# all_proen2.net
KiCad netlist of a schematic drawn in EAGLE
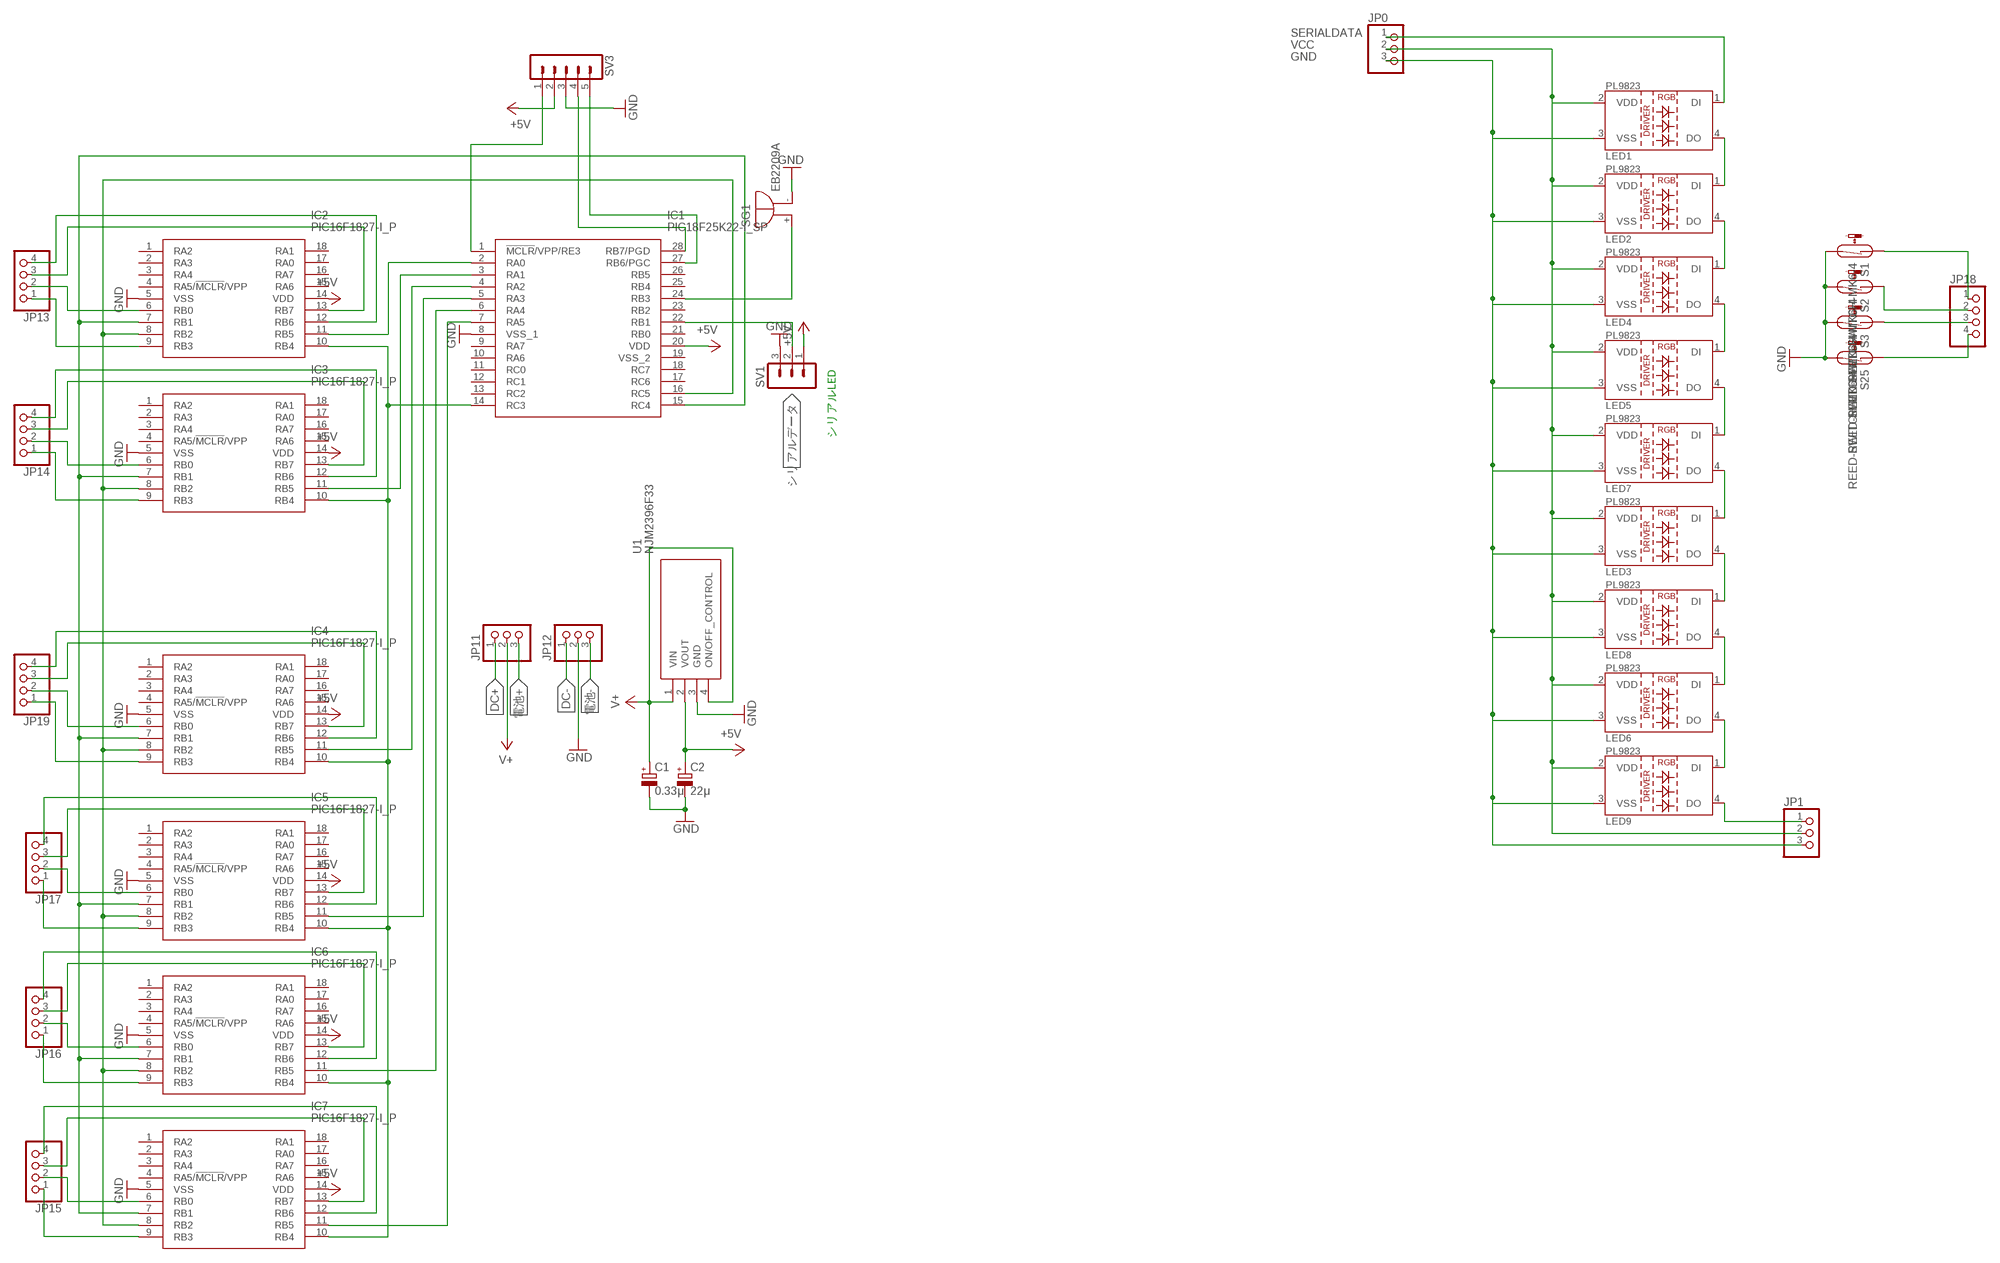
[diagram p0: schematic, sheet 1]

(export (version "E")
  (design (tool "Eeschema 10.0.6"))
  (components
    (comp (ref "C1")
      (value "0.33μ")
      (footprint "eagle-import:E2,5-6E")
      (libsource (lib "eagle-import") (part "CPOL-EUE2,5-6E"))
    )
    (comp (ref "C2")
      (value "22μ")
      (footprint "eagle-import:E2,5-6E")
      (libsource (lib "eagle-import") (part "CPOL-EUE2,5-6E"))
    )
    (comp (ref "IC1")
      (value "PIC18F25K22-I_SP")
      (footprint "eagle-import:DIP794W56P254L3486H508Q28N")
      (fields
        (field (name "MANUFACTURER_PART_NUMBER") "PIC18F25K22-I/SP")
        (field (name "MOUSER_PART_NUMBER") "579-PIC18F25K22ISP")
        (field (name "RS_PART_NUMBER") "8231142")
      )
      (libsource (lib "eagle-import") (part "PIC18F25K22-I_SP"))
    )
    (comp (ref "IC2")
      (value "PIC16F1827-I_P")
      (footprint "eagle-import:DIP794W56P254L2286H533Q18N")
      (fields
        (field (name "MANUFACTURER_PART_NUMBER") "PIC16F1827-I/P")
        (field (name "MOUSER_PART_NUMBER") "579-PIC16F1827-I/P")
        (field (name "RS_PART_NUMBER") "6988959P")
      )
      (libsource (lib "eagle-import") (part "PIC16F1827-I_P"))
    )
    (comp (ref "IC3")
      (value "PIC16F1827-I_P")
      (footprint "eagle-import:DIP794W56P254L2286H533Q18N")
      (fields
        (field (name "MANUFACTURER_PART_NUMBER") "PIC16F1827-I/P")
        (field (name "MOUSER_PART_NUMBER") "579-PIC16F1827-I/P")
        (field (name "RS_PART_NUMBER") "6988959P")
      )
      (libsource (lib "eagle-import") (part "PIC16F1827-I_P"))
    )
    (comp (ref "IC4")
      (value "PIC16F1827-I_P")
      (footprint "eagle-import:DIP794W56P254L2286H533Q18N")
      (fields
        (field (name "MANUFACTURER_PART_NUMBER") "PIC16F1827-I/P")
        (field (name "MOUSER_PART_NUMBER") "579-PIC16F1827-I/P")
        (field (name "RS_PART_NUMBER") "6988959P")
      )
      (libsource (lib "eagle-import") (part "PIC16F1827-I_P"))
    )
    (comp (ref "IC5")
      (value "PIC16F1827-I_P")
      (footprint "eagle-import:DIP794W56P254L2286H533Q18N")
      (fields
        (field (name "MANUFACTURER_PART_NUMBER") "PIC16F1827-I/P")
        (field (name "MOUSER_PART_NUMBER") "579-PIC16F1827-I/P")
        (field (name "RS_PART_NUMBER") "6988959P")
      )
      (libsource (lib "eagle-import") (part "PIC16F1827-I_P"))
    )
    (comp (ref "IC6")
      (value "PIC16F1827-I_P")
      (footprint "eagle-import:DIP794W56P254L2286H533Q18N")
      (fields
        (field (name "MANUFACTURER_PART_NUMBER") "PIC16F1827-I/P")
        (field (name "MOUSER_PART_NUMBER") "579-PIC16F1827-I/P")
        (field (name "RS_PART_NUMBER") "6988959P")
      )
      (libsource (lib "eagle-import") (part "PIC16F1827-I_P"))
    )
    (comp (ref "IC7")
      (value "PIC16F1827-I_P")
      (footprint "eagle-import:DIP794W56P254L2286H533Q18N")
      (fields
        (field (name "MANUFACTURER_PART_NUMBER") "PIC16F1827-I/P")
        (field (name "MOUSER_PART_NUMBER") "579-PIC16F1827-I/P")
        (field (name "RS_PART_NUMBER") "6988959P")
      )
      (libsource (lib "eagle-import") (part "PIC16F1827-I_P"))
    )
    (comp (ref "JP0")
      (value "PINHD-1X3")
      (footprint "eagle-import:1X03")
      (libsource (lib "eagle-import") (part "PINHD-1X3"))
    )
    (comp (ref "JP1")
      (value "PINHD-1X3")
      (footprint "eagle-import:1X03")
      (libsource (lib "eagle-import") (part "PINHD-1X3"))
    )
    (comp (ref "JP11")
      (value "PINHD-1X3")
      (footprint "eagle-import:1X03")
      (libsource (lib "eagle-import") (part "PINHD-1X3"))
    )
    (comp (ref "JP12")
      (value "PINHD-1X3")
      (footprint "eagle-import:1X03")
      (libsource (lib "eagle-import") (part "PINHD-1X3"))
    )
    (comp (ref "JP13")
      (value "PINHD-1X4")
      (footprint "eagle-import:1X04")
      (libsource (lib "eagle-import") (part "PINHD-1X4"))
    )
    (comp (ref "JP14")
      (value "PINHD-1X4")
      (footprint "eagle-import:1X04")
      (libsource (lib "eagle-import") (part "PINHD-1X4"))
    )
    (comp (ref "JP15")
      (value "PINHD-1X4")
      (footprint "eagle-import:1X04")
      (libsource (lib "eagle-import") (part "PINHD-1X4"))
    )
    (comp (ref "JP16")
      (value "PINHD-1X4")
      (footprint "eagle-import:1X04")
      (libsource (lib "eagle-import") (part "PINHD-1X4"))
    )
    (comp (ref "JP17")
      (value "PINHD-1X4")
      (footprint "eagle-import:1X04")
      (libsource (lib "eagle-import") (part "PINHD-1X4"))
    )
    (comp (ref "JP18")
      (value "PINHD-1X4")
      (footprint "eagle-import:1X04")
      (libsource (lib "eagle-import") (part "PINHD-1X4"))
    )
    (comp (ref "JP19")
      (value "PINHD-1X4")
      (footprint "eagle-import:1X04")
      (libsource (lib "eagle-import") (part "PINHD-1X4"))
    )
    (comp (ref "LED1")
      (value "LED-PL9823-F5")
      (footprint "eagle-import:LED-PL9823-F5")
      (libsource (lib "eagle-import") (part "LED-PL9823-F5"))
    )
    (comp (ref "LED2")
      (value "LED-PL9823-F5")
      (footprint "eagle-import:LED-PL9823-F5")
      (libsource (lib "eagle-import") (part "LED-PL9823-F5"))
    )
    (comp (ref "LED3")
      (value "LED-PL9823-F5")
      (footprint "eagle-import:LED-PL9823-F5")
      (libsource (lib "eagle-import") (part "LED-PL9823-F5"))
    )
    (comp (ref "LED4")
      (value "LED-PL9823-F5")
      (footprint "eagle-import:LED-PL9823-F5")
      (libsource (lib "eagle-import") (part "LED-PL9823-F5"))
    )
    (comp (ref "LED5")
      (value "LED-PL9823-F5")
      (footprint "eagle-import:LED-PL9823-F5")
      (libsource (lib "eagle-import") (part "LED-PL9823-F5"))
    )
    (comp (ref "LED6")
      (value "LED-PL9823-F5")
      (footprint "eagle-import:LED-PL9823-F5")
      (libsource (lib "eagle-import") (part "LED-PL9823-F5"))
    )
    (comp (ref "LED7")
      (value "LED-PL9823-F5")
      (footprint "eagle-import:LED-PL9823-F5")
      (libsource (lib "eagle-import") (part "LED-PL9823-F5"))
    )
    (comp (ref "LED8")
      (value "LED-PL9823-F5")
      (footprint "eagle-import:LED-PL9823-F5")
      (libsource (lib "eagle-import") (part "LED-PL9823-F5"))
    )
    (comp (ref "LED9")
      (value "LED-PL9823-F5")
      (footprint "eagle-import:LED-PL9823-F5")
      (libsource (lib "eagle-import") (part "LED-PL9823-F5"))
    )
    (comp (ref "S1")
      (value "REED-SWITCH-MK6-4")
      (footprint "eagle-import:MK6-4")
      (libsource (lib "eagle-import") (part "REED-SWITCH-MK6-4"))
    )
    (comp (ref "S2")
      (value "REED-SWITCH-MK6-4")
      (footprint "eagle-import:MK6-4")
      (libsource (lib "eagle-import") (part "REED-SWITCH-MK6-4"))
    )
    (comp (ref "S3")
      (value "REED-SWITCH-MK6-4")
      (footprint "eagle-import:MK6-4")
      (libsource (lib "eagle-import") (part "REED-SWITCH-MK6-4"))
    )
    (comp (ref "S25")
      (value "REED-SWITCH-MK6-4")
      (footprint "eagle-import:MK6-4")
      (libsource (lib "eagle-import") (part "REED-SWITCH-MK6-4"))
    )
    (comp (ref "SG1")
      (value "EB2209A")
      (footprint "eagle-import:EB2209A")
      (libsource (lib "eagle-import") (part "EB2209A"))
    )
    (comp (ref "SV1")
      (value "MA03-1")
      (footprint "eagle-import:MA03-1")
      (libsource (lib "eagle-import") (part "MA03-1"))
    )
    (comp (ref "SV3")
      (value "MA05-1")
      (footprint "eagle-import:MA05-1")
      (libsource (lib "eagle-import") (part "MA05-1"))
    )
    (comp (ref "U1")
      (value "NJM2396F33")
      (footprint "eagle-import:TO254P480X1000X1900-4P")
      (fields (field (name "RS_PART_NUMBER") "6641023"))
      (libsource (lib "eagle-import") (part "NJM2396F33"))
    )
  )
  (nets
    (net (code "1") (name "+5V") (class "Default")
      (node (ref "C2") (pin "+") (pinfunction "+_+") (pintype "passive"))
      (node (ref "IC1") (pin "20") (pinfunction "VDD_20") (pintype "bidirectional"))
      (node (ref "IC2") (pin "14") (pinfunction "VDD_14") (pintype "bidirectional"))
      (node (ref "IC3") (pin "14") (pinfunction "VDD_14") (pintype "bidirectional"))
      (node (ref "IC4") (pin "14") (pinfunction "VDD_14") (pintype "bidirectional"))
      (node (ref "IC5") (pin "14") (pinfunction "VDD_14") (pintype "bidirectional"))
      (node (ref "IC6") (pin "14") (pinfunction "VDD_14") (pintype "bidirectional"))
      (node (ref "IC7") (pin "14") (pinfunction "VDD_14") (pintype "bidirectional"))
      (node (ref "SV1") (pin "1") (pinfunction "1_1") (pintype "passive"))
      (node (ref "SV3") (pin "2") (pinfunction "2_2") (pintype "passive"))
      (node (ref "U1") (pin "2") (pinfunction "VOUT_2") (pintype "bidirectional"))
    )
    (net (code "2") (name "/SERIALDATA") (class "Default")
      (node (ref "JP0") (pin "1") (pinfunction "1_1") (pintype "passive"))
      (node (ref "LED1") (pin "1") (pinfunction "DI_1") (pintype "bidirectional"))
    )
    (net (code "3") (name "/VCC") (class "Default")
      (node (ref "JP0") (pin "2") (pinfunction "2_2") (pintype "passive"))
      (node (ref "JP1") (pin "2") (pinfunction "2_2") (pintype "passive"))
      (node (ref "LED1") (pin "2") (pinfunction "VDD_2") (pintype "bidirectional"))
      (node (ref "LED2") (pin "2") (pinfunction "VDD_2") (pintype "bidirectional"))
      (node (ref "LED3") (pin "2") (pinfunction "VDD_2") (pintype "bidirectional"))
      (node (ref "LED4") (pin "2") (pinfunction "VDD_2") (pintype "bidirectional"))
      (node (ref "LED5") (pin "2") (pinfunction "VDD_2") (pintype "bidirectional"))
      (node (ref "LED6") (pin "2") (pinfunction "VDD_2") (pintype "bidirectional"))
      (node (ref "LED7") (pin "2") (pinfunction "VDD_2") (pintype "bidirectional"))
      (node (ref "LED8") (pin "2") (pinfunction "VDD_2") (pintype "bidirectional"))
      (node (ref "LED9") (pin "2") (pinfunction "VDD_2") (pintype "bidirectional"))
    )
    (net (code "4") (name "DC+") (class "Default")
      (node (ref "JP11") (pin "1") (pinfunction "1_1") (pintype "passive"))
    )
    (net (code "5") (name "DC-") (class "Default")
      (node (ref "JP12") (pin "1") (pinfunction "1_1") (pintype "passive"))
    )
    (net (code "6") (name "GND") (class "Default")
      (node (ref "C1") (pin "-") (pinfunction "-_-") (pintype "passive"))
      (node (ref "C2") (pin "-") (pinfunction "-_-") (pintype "passive"))
      (node (ref "IC1") (pin "8") (pinfunction "VSS_1_8") (pintype "bidirectional"))
      (node (ref "IC2") (pin "5") (pinfunction "VSS_5") (pintype "bidirectional"))
      (node (ref "IC3") (pin "5") (pinfunction "VSS_5") (pintype "bidirectional"))
      (node (ref "IC4") (pin "5") (pinfunction "VSS_5") (pintype "bidirectional"))
      (node (ref "IC5") (pin "5") (pinfunction "VSS_5") (pintype "bidirectional"))
      (node (ref "IC6") (pin "5") (pinfunction "VSS_5") (pintype "bidirectional"))
      (node (ref "IC7") (pin "5") (pinfunction "VSS_5") (pintype "bidirectional"))
      (node (ref "JP0") (pin "3") (pinfunction "3_3") (pintype "passive"))
      (node (ref "JP1") (pin "3") (pinfunction "3_3") (pintype "passive"))
      (node (ref "JP12") (pin "2") (pinfunction "2_2") (pintype "passive"))
      (node (ref "LED1") (pin "3") (pinfunction "VSS_3") (pintype "bidirectional"))
      (node (ref "LED2") (pin "3") (pinfunction "VSS_3") (pintype "bidirectional"))
      (node (ref "LED3") (pin "3") (pinfunction "VSS_3") (pintype "bidirectional"))
      (node (ref "LED4") (pin "3") (pinfunction "VSS_3") (pintype "bidirectional"))
      (node (ref "LED5") (pin "3") (pinfunction "VSS_3") (pintype "bidirectional"))
      (node (ref "LED6") (pin "3") (pinfunction "VSS_3") (pintype "bidirectional"))
      (node (ref "LED7") (pin "3") (pinfunction "VSS_3") (pintype "bidirectional"))
      (node (ref "LED8") (pin "3") (pinfunction "VSS_3") (pintype "bidirectional"))
      (node (ref "LED9") (pin "3") (pinfunction "VSS_3") (pintype "bidirectional"))
      (node (ref "S1") (pin "2") (pinfunction "2_2") (pintype "passive"))
      (node (ref "S2") (pin "2") (pinfunction "2_2") (pintype "passive"))
      (node (ref "S25") (pin "2") (pinfunction "2_2") (pintype "passive"))
      (node (ref "S3") (pin "2") (pinfunction "2_2") (pintype "passive"))
      (node (ref "SG1") (pin "-") (pinfunction "-_-") (pintype "passive"))
      (node (ref "SV1") (pin "3") (pinfunction "3_3") (pintype "passive"))
      (node (ref "SV3") (pin "3") (pinfunction "3_3") (pintype "passive"))
      (node (ref "U1") (pin "3") (pinfunction "GND_3") (pintype "bidirectional"))
    )
    (net (code "7") (name "Net-(IC1-RA0)") (class "Default")
      (node (ref "IC1") (pin "2") (pinfunction "RA0_2") (pintype "bidirectional"))
      (node (ref "IC2") (pin "11") (pinfunction "RB5_11") (pintype "bidirectional"))
    )
    (net (code "8") (name "Net-(IC1-RA1)") (class "Default")
      (node (ref "IC1") (pin "3") (pinfunction "RA1_3") (pintype "bidirectional"))
      (node (ref "IC3") (pin "11") (pinfunction "RB5_11") (pintype "bidirectional"))
    )
    (net (code "9") (name "Net-(IC1-RA2)") (class "Default")
      (node (ref "IC1") (pin "4") (pinfunction "RA2_4") (pintype "bidirectional"))
      (node (ref "IC4") (pin "11") (pinfunction "RB5_11") (pintype "bidirectional"))
    )
    (net (code "10") (name "Net-(IC1-RA3)") (class "Default")
      (node (ref "IC1") (pin "5") (pinfunction "RA3_5") (pintype "bidirectional"))
      (node (ref "IC5") (pin "11") (pinfunction "RB5_11") (pintype "bidirectional"))
    )
    (net (code "11") (name "Net-(IC1-RA4)") (class "Default")
      (node (ref "IC1") (pin "6") (pinfunction "RA4_6") (pintype "bidirectional"))
      (node (ref "IC6") (pin "11") (pinfunction "RB5_11") (pintype "bidirectional"))
    )
    (net (code "12") (name "Net-(IC1-RA5)") (class "Default")
      (node (ref "IC1") (pin "7") (pinfunction "RA5_7") (pintype "bidirectional"))
      (node (ref "IC7") (pin "11") (pinfunction "RB5_11") (pintype "bidirectional"))
    )
    (net (code "13") (name "Net-(IC1-RB3)") (class "Default")
      (node (ref "IC1") (pin "24") (pinfunction "RB3_24") (pintype "bidirectional"))
      (node (ref "SG1") (pin "+") (pinfunction "+_+") (pintype "passive"))
    )
    (net (code "14") (name "Net-(IC1-RB6{slash}PGC)") (class "Default")
      (node (ref "IC1") (pin "27") (pinfunction "RB6/PGC_27") (pintype "bidirectional"))
      (node (ref "SV3") (pin "5") (pinfunction "5_5") (pintype "passive"))
    )
    (net (code "15") (name "Net-(IC1-RB7{slash}PGD)") (class "Default")
      (node (ref "IC1") (pin "28") (pinfunction "RB7/PGD_28") (pintype "bidirectional"))
      (node (ref "SV3") (pin "4") (pinfunction "4_4") (pintype "passive"))
    )
    (net (code "16") (name "Net-(IC1-RC3)") (class "Default")
      (node (ref "IC1") (pin "14") (pinfunction "RC3_14") (pintype "bidirectional"))
      (node (ref "IC2") (pin "10") (pinfunction "RB4_10") (pintype "bidirectional"))
      (node (ref "IC3") (pin "10") (pinfunction "RB4_10") (pintype "bidirectional"))
      (node (ref "IC4") (pin "10") (pinfunction "RB4_10") (pintype "bidirectional"))
      (node (ref "IC5") (pin "10") (pinfunction "RB4_10") (pintype "bidirectional"))
      (node (ref "IC6") (pin "10") (pinfunction "RB4_10") (pintype "bidirectional"))
      (node (ref "IC7") (pin "10") (pinfunction "RB4_10") (pintype "bidirectional"))
    )
    (net (code "17") (name "Net-(IC1-RC4)") (class "Default")
      (node (ref "IC1") (pin "15") (pinfunction "RC4_15") (pintype "bidirectional"))
      (node (ref "IC2") (pin "7") (pinfunction "RB1_7") (pintype "bidirectional"))
      (node (ref "IC3") (pin "7") (pinfunction "RB1_7") (pintype "bidirectional"))
      (node (ref "IC4") (pin "7") (pinfunction "RB1_7") (pintype "bidirectional"))
      (node (ref "IC5") (pin "7") (pinfunction "RB1_7") (pintype "bidirectional"))
      (node (ref "IC6") (pin "7") (pinfunction "RB1_7") (pintype "bidirectional"))
      (node (ref "IC7") (pin "7") (pinfunction "RB1_7") (pintype "bidirectional"))
    )
    (net (code "18") (name "Net-(IC1-RC5)") (class "Default")
      (node (ref "IC1") (pin "16") (pinfunction "RC5_16") (pintype "bidirectional"))
      (node (ref "IC2") (pin "8") (pinfunction "RB2_8") (pintype "bidirectional"))
      (node (ref "IC3") (pin "8") (pinfunction "RB2_8") (pintype "bidirectional"))
      (node (ref "IC4") (pin "8") (pinfunction "RB2_8") (pintype "bidirectional"))
      (node (ref "IC5") (pin "8") (pinfunction "RB2_8") (pintype "bidirectional"))
      (node (ref "IC6") (pin "8") (pinfunction "RB2_8") (pintype "bidirectional"))
      (node (ref "IC7") (pin "8") (pinfunction "RB2_8") (pintype "bidirectional"))
    )
    (net (code "19") (name "Net-(IC1-~{MCLR}{slash}VPP{slash}RE3)") (class "Default")
      (node (ref "IC1") (pin "1") (pinfunction "~{MCLR}/VPP/RE3_1") (pintype "bidirectional"))
      (node (ref "SV3") (pin "1") (pinfunction "1_1") (pintype "passive"))
    )
    (net (code "20") (name "Net-(IC2-RB0)") (class "Default")
      (node (ref "IC2") (pin "6") (pinfunction "RB0_6") (pintype "bidirectional"))
      (node (ref "JP13") (pin "2") (pinfunction "2_2") (pintype "passive"))
    )
    (net (code "21") (name "Net-(IC2-RB3)") (class "Default")
      (node (ref "IC2") (pin "9") (pinfunction "RB3_9") (pintype "bidirectional"))
      (node (ref "JP13") (pin "1") (pinfunction "1_1") (pintype "passive"))
    )
    (net (code "22") (name "Net-(IC2-RB6)") (class "Default")
      (node (ref "IC2") (pin "12") (pinfunction "RB6_12") (pintype "bidirectional"))
      (node (ref "JP13") (pin "4") (pinfunction "4_4") (pintype "passive"))
    )
    (net (code "23") (name "Net-(IC2-RB7)") (class "Default")
      (node (ref "IC2") (pin "13") (pinfunction "RB7_13") (pintype "bidirectional"))
      (node (ref "JP13") (pin "3") (pinfunction "3_3") (pintype "passive"))
    )
    (net (code "24") (name "Net-(IC3-RB0)") (class "Default")
      (node (ref "IC3") (pin "6") (pinfunction "RB0_6") (pintype "bidirectional"))
      (node (ref "JP14") (pin "2") (pinfunction "2_2") (pintype "passive"))
    )
    (net (code "25") (name "Net-(IC3-RB3)") (class "Default")
      (node (ref "IC3") (pin "9") (pinfunction "RB3_9") (pintype "bidirectional"))
      (node (ref "JP14") (pin "1") (pinfunction "1_1") (pintype "passive"))
    )
    (net (code "26") (name "Net-(IC3-RB6)") (class "Default")
      (node (ref "IC3") (pin "12") (pinfunction "RB6_12") (pintype "bidirectional"))
      (node (ref "JP14") (pin "4") (pinfunction "4_4") (pintype "passive"))
    )
    (net (code "27") (name "Net-(IC3-RB7)") (class "Default")
      (node (ref "IC3") (pin "13") (pinfunction "RB7_13") (pintype "bidirectional"))
      (node (ref "JP14") (pin "3") (pinfunction "3_3") (pintype "passive"))
    )
    (net (code "28") (name "Net-(IC4-RB0)") (class "Default")
      (node (ref "IC4") (pin "6") (pinfunction "RB0_6") (pintype "bidirectional"))
      (node (ref "JP19") (pin "2") (pinfunction "2_2") (pintype "passive"))
    )
    (net (code "29") (name "Net-(IC4-RB3)") (class "Default")
      (node (ref "IC4") (pin "9") (pinfunction "RB3_9") (pintype "bidirectional"))
      (node (ref "JP19") (pin "1") (pinfunction "1_1") (pintype "passive"))
    )
    (net (code "30") (name "Net-(IC4-RB6)") (class "Default")
      (node (ref "IC4") (pin "12") (pinfunction "RB6_12") (pintype "bidirectional"))
      (node (ref "JP19") (pin "4") (pinfunction "4_4") (pintype "passive"))
    )
    (net (code "31") (name "Net-(IC4-RB7)") (class "Default")
      (node (ref "IC4") (pin "13") (pinfunction "RB7_13") (pintype "bidirectional"))
      (node (ref "JP19") (pin "3") (pinfunction "3_3") (pintype "passive"))
    )
    (net (code "32") (name "Net-(IC5-RB0)") (class "Default")
      (node (ref "IC5") (pin "6") (pinfunction "RB0_6") (pintype "bidirectional"))
      (node (ref "JP17") (pin "2") (pinfunction "2_2") (pintype "passive"))
    )
    (net (code "33") (name "Net-(IC5-RB3)") (class "Default")
      (node (ref "IC5") (pin "9") (pinfunction "RB3_9") (pintype "bidirectional"))
      (node (ref "JP17") (pin "1") (pinfunction "1_1") (pintype "passive"))
    )
    (net (code "34") (name "Net-(IC5-RB6)") (class "Default")
      (node (ref "IC5") (pin "12") (pinfunction "RB6_12") (pintype "bidirectional"))
      (node (ref "JP17") (pin "4") (pinfunction "4_4") (pintype "passive"))
    )
    (net (code "35") (name "Net-(IC5-RB7)") (class "Default")
      (node (ref "IC5") (pin "13") (pinfunction "RB7_13") (pintype "bidirectional"))
      (node (ref "JP17") (pin "3") (pinfunction "3_3") (pintype "passive"))
    )
    (net (code "36") (name "Net-(IC6-RB0)") (class "Default")
      (node (ref "IC6") (pin "6") (pinfunction "RB0_6") (pintype "bidirectional"))
      (node (ref "JP16") (pin "2") (pinfunction "2_2") (pintype "passive"))
    )
    (net (code "37") (name "Net-(IC6-RB3)") (class "Default")
      (node (ref "IC6") (pin "9") (pinfunction "RB3_9") (pintype "bidirectional"))
      (node (ref "JP16") (pin "1") (pinfunction "1_1") (pintype "passive"))
    )
    (net (code "38") (name "Net-(IC6-RB6)") (class "Default")
      (node (ref "IC6") (pin "12") (pinfunction "RB6_12") (pintype "bidirectional"))
      (node (ref "JP16") (pin "4") (pinfunction "4_4") (pintype "passive"))
    )
    (net (code "39") (name "Net-(IC6-RB7)") (class "Default")
      (node (ref "IC6") (pin "13") (pinfunction "RB7_13") (pintype "bidirectional"))
      (node (ref "JP16") (pin "3") (pinfunction "3_3") (pintype "passive"))
    )
    (net (code "40") (name "Net-(IC7-RB0)") (class "Default")
      (node (ref "IC7") (pin "6") (pinfunction "RB0_6") (pintype "bidirectional"))
      (node (ref "JP15") (pin "2") (pinfunction "2_2") (pintype "passive"))
    )
    (net (code "41") (name "Net-(IC7-RB3)") (class "Default")
      (node (ref "IC7") (pin "9") (pinfunction "RB3_9") (pintype "bidirectional"))
      (node (ref "JP15") (pin "1") (pinfunction "1_1") (pintype "passive"))
    )
    (net (code "42") (name "Net-(IC7-RB6)") (class "Default")
      (node (ref "IC7") (pin "12") (pinfunction "RB6_12") (pintype "bidirectional"))
      (node (ref "JP15") (pin "4") (pinfunction "4_4") (pintype "passive"))
    )
    (net (code "43") (name "Net-(IC7-RB7)") (class "Default")
      (node (ref "IC7") (pin "13") (pinfunction "RB7_13") (pintype "bidirectional"))
      (node (ref "JP15") (pin "3") (pinfunction "3_3") (pintype "passive"))
    )
    (net (code "44") (name "Net-(JP18-Pad1)") (class "Default")
      (node (ref "JP18") (pin "1") (pinfunction "1_1") (pintype "passive"))
      (node (ref "S1") (pin "1") (pinfunction "1_1") (pintype "passive"))
    )
    (net (code "45") (name "Net-(JP18-Pad2)") (class "Default")
      (node (ref "JP18") (pin "2") (pinfunction "2_2") (pintype "passive"))
      (node (ref "S2") (pin "1") (pinfunction "1_1") (pintype "passive"))
    )
    (net (code "46") (name "Net-(JP18-Pad3)") (class "Default")
      (node (ref "JP18") (pin "3") (pinfunction "3_3") (pintype "passive"))
      (node (ref "S3") (pin "1") (pinfunction "1_1") (pintype "passive"))
    )
    (net (code "47") (name "Net-(JP18-Pad4)") (class "Default")
      (node (ref "JP18") (pin "4") (pinfunction "4_4") (pintype "passive"))
      (node (ref "S25") (pin "1") (pinfunction "1_1") (pintype "passive"))
    )
    (net (code "48") (name "Net-(LED1-DO)") (class "Default")
      (node (ref "LED1") (pin "4") (pinfunction "DO_4") (pintype "bidirectional"))
      (node (ref "LED2") (pin "1") (pinfunction "DI_1") (pintype "bidirectional"))
    )
    (net (code "49") (name "Net-(LED2-DO)") (class "Default")
      (node (ref "LED2") (pin "4") (pinfunction "DO_4") (pintype "bidirectional"))
      (node (ref "LED4") (pin "1") (pinfunction "DI_1") (pintype "bidirectional"))
    )
    (net (code "50") (name "Net-(LED3-DI)") (class "Default")
      (node (ref "LED3") (pin "1") (pinfunction "DI_1") (pintype "bidirectional"))
      (node (ref "LED7") (pin "4") (pinfunction "DO_4") (pintype "bidirectional"))
    )
    (net (code "51") (name "Net-(LED3-DO)") (class "Default")
      (node (ref "LED3") (pin "4") (pinfunction "DO_4") (pintype "bidirectional"))
      (node (ref "LED8") (pin "1") (pinfunction "DI_1") (pintype "bidirectional"))
    )
    (net (code "52") (name "Net-(LED4-DO)") (class "Default")
      (node (ref "LED4") (pin "4") (pinfunction "DO_4") (pintype "bidirectional"))
      (node (ref "LED5") (pin "1") (pinfunction "DI_1") (pintype "bidirectional"))
    )
    (net (code "53") (name "Net-(LED5-DO)") (class "Default")
      (node (ref "LED5") (pin "4") (pinfunction "DO_4") (pintype "bidirectional"))
      (node (ref "LED7") (pin "1") (pinfunction "DI_1") (pintype "bidirectional"))
    )
    (net (code "54") (name "Net-(LED6-DI)") (class "Default")
      (node (ref "LED6") (pin "1") (pinfunction "DI_1") (pintype "bidirectional"))
      (node (ref "LED8") (pin "4") (pinfunction "DO_4") (pintype "bidirectional"))
    )
    (net (code "55") (name "Net-(LED6-DO)") (class "Default")
      (node (ref "LED6") (pin "4") (pinfunction "DO_4") (pintype "bidirectional"))
      (node (ref "LED9") (pin "1") (pinfunction "DI_1") (pintype "bidirectional"))
    )
    (net (code "56") (name "Net-(LED9-DO)") (class "Default")
      (node (ref "JP1") (pin "1") (pinfunction "1_1") (pintype "passive"))
      (node (ref "LED9") (pin "4") (pinfunction "DO_4") (pintype "bidirectional"))
    )
    (net (code "57") (name "V+") (class "Default")
      (node (ref "C1") (pin "+") (pinfunction "+_+") (pintype "passive"))
      (node (ref "JP11") (pin "2") (pinfunction "2_2") (pintype "passive"))
      (node (ref "U1") (pin "1") (pinfunction "VIN_1") (pintype "bidirectional"))
      (node (ref "U1") (pin "4") (pinfunction "ON/OFF_CONTROL_4") (pintype "bidirectional"))
    )
    (net (code "58") (name "unconnected-(IC1-RA6-Pad10)") (class "Default")
      (node (ref "IC1") (pin "10") (pinfunction "RA6_10") (pintype "bidirectional"))
    )
    (net (code "59") (name "unconnected-(IC1-RA7-Pad9)") (class "Default")
      (node (ref "IC1") (pin "9") (pinfunction "RA7_9") (pintype "bidirectional"))
    )
    (net (code "60") (name "unconnected-(IC1-RB0-Pad21)") (class "Default")
      (node (ref "IC1") (pin "21") (pinfunction "RB0_21") (pintype "bidirectional"))
    )
    (net (code "61") (name "unconnected-(IC1-RB2-Pad23)") (class "Default")
      (node (ref "IC1") (pin "23") (pinfunction "RB2_23") (pintype "bidirectional"))
    )
    (net (code "62") (name "unconnected-(IC1-RB4-Pad25)") (class "Default")
      (node (ref "IC1") (pin "25") (pinfunction "RB4_25") (pintype "bidirectional"))
    )
    (net (code "63") (name "unconnected-(IC1-RB5-Pad26)") (class "Default")
      (node (ref "IC1") (pin "26") (pinfunction "RB5_26") (pintype "bidirectional"))
    )
    (net (code "64") (name "unconnected-(IC1-RC0-Pad11)") (class "Default")
      (node (ref "IC1") (pin "11") (pinfunction "RC0_11") (pintype "bidirectional"))
    )
    (net (code "65") (name "unconnected-(IC1-RC1-Pad12)") (class "Default")
      (node (ref "IC1") (pin "12") (pinfunction "RC1_12") (pintype "bidirectional"))
    )
    (net (code "66") (name "unconnected-(IC1-RC2-Pad13)") (class "Default")
      (node (ref "IC1") (pin "13") (pinfunction "RC2_13") (pintype "bidirectional"))
    )
    (net (code "67") (name "unconnected-(IC1-RC6-Pad17)") (class "Default")
      (node (ref "IC1") (pin "17") (pinfunction "RC6_17") (pintype "bidirectional"))
    )
    (net (code "68") (name "unconnected-(IC1-RC7-Pad18)") (class "Default")
      (node (ref "IC1") (pin "18") (pinfunction "RC7_18") (pintype "bidirectional"))
    )
    (net (code "69") (name "unconnected-(IC1-VSS_2-Pad19)") (class "Default")
      (node (ref "IC1") (pin "19") (pinfunction "VSS_2_19") (pintype "bidirectional"))
    )
    (net (code "70") (name "unconnected-(IC2-RA0-Pad17)") (class "Default")
      (node (ref "IC2") (pin "17") (pinfunction "RA0_17") (pintype "bidirectional"))
    )
    (net (code "71") (name "unconnected-(IC2-RA1-Pad18)") (class "Default")
      (node (ref "IC2") (pin "18") (pinfunction "RA1_18") (pintype "bidirectional"))
    )
    (net (code "72") (name "unconnected-(IC2-RA2-Pad1)") (class "Default")
      (node (ref "IC2") (pin "1") (pinfunction "RA2_1") (pintype "bidirectional"))
    )
    (net (code "73") (name "unconnected-(IC2-RA3-Pad2)") (class "Default")
      (node (ref "IC2") (pin "2") (pinfunction "RA3_2") (pintype "bidirectional"))
    )
    (net (code "74") (name "unconnected-(IC2-RA4-Pad3)") (class "Default")
      (node (ref "IC2") (pin "3") (pinfunction "RA4_3") (pintype "bidirectional"))
    )
    (net (code "75") (name "unconnected-(IC2-RA5{slash}~{MCLR}{slash}VPP-Pad4)") (class "Default")
      (node (ref "IC2") (pin "4") (pinfunction "RA5/~{MCLR}/VPP_4") (pintype "bidirectional"))
    )
    (net (code "76") (name "unconnected-(IC2-RA6-Pad15)") (class "Default")
      (node (ref "IC2") (pin "15") (pinfunction "RA6_15") (pintype "bidirectional"))
    )
    (net (code "77") (name "unconnected-(IC2-RA7-Pad16)") (class "Default")
      (node (ref "IC2") (pin "16") (pinfunction "RA7_16") (pintype "bidirectional"))
    )
    (net (code "78") (name "unconnected-(IC3-RA0-Pad17)") (class "Default")
      (node (ref "IC3") (pin "17") (pinfunction "RA0_17") (pintype "bidirectional"))
    )
    (net (code "79") (name "unconnected-(IC3-RA1-Pad18)") (class "Default")
      (node (ref "IC3") (pin "18") (pinfunction "RA1_18") (pintype "bidirectional"))
    )
    (net (code "80") (name "unconnected-(IC3-RA2-Pad1)") (class "Default")
      (node (ref "IC3") (pin "1") (pinfunction "RA2_1") (pintype "bidirectional"))
    )
    (net (code "81") (name "unconnected-(IC3-RA3-Pad2)") (class "Default")
      (node (ref "IC3") (pin "2") (pinfunction "RA3_2") (pintype "bidirectional"))
    )
    (net (code "82") (name "unconnected-(IC3-RA4-Pad3)") (class "Default")
      (node (ref "IC3") (pin "3") (pinfunction "RA4_3") (pintype "bidirectional"))
    )
    (net (code "83") (name "unconnected-(IC3-RA5{slash}~{MCLR}{slash}VPP-Pad4)") (class "Default")
      (node (ref "IC3") (pin "4") (pinfunction "RA5/~{MCLR}/VPP_4") (pintype "bidirectional"))
    )
    (net (code "84") (name "unconnected-(IC3-RA6-Pad15)") (class "Default")
      (node (ref "IC3") (pin "15") (pinfunction "RA6_15") (pintype "bidirectional"))
    )
    (net (code "85") (name "unconnected-(IC3-RA7-Pad16)") (class "Default")
      (node (ref "IC3") (pin "16") (pinfunction "RA7_16") (pintype "bidirectional"))
    )
    (net (code "86") (name "unconnected-(IC4-RA0-Pad17)") (class "Default")
      (node (ref "IC4") (pin "17") (pinfunction "RA0_17") (pintype "bidirectional"))
    )
    (net (code "87") (name "unconnected-(IC4-RA1-Pad18)") (class "Default")
      (node (ref "IC4") (pin "18") (pinfunction "RA1_18") (pintype "bidirectional"))
    )
    (net (code "88") (name "unconnected-(IC4-RA2-Pad1)") (class "Default")
      (node (ref "IC4") (pin "1") (pinfunction "RA2_1") (pintype "bidirectional"))
    )
    (net (code "89") (name "unconnected-(IC4-RA3-Pad2)") (class "Default")
      (node (ref "IC4") (pin "2") (pinfunction "RA3_2") (pintype "bidirectional"))
    )
    (net (code "90") (name "unconnected-(IC4-RA4-Pad3)") (class "Default")
      (node (ref "IC4") (pin "3") (pinfunction "RA4_3") (pintype "bidirectional"))
    )
    (net (code "91") (name "unconnected-(IC4-RA5{slash}~{MCLR}{slash}VPP-Pad4)") (class "Default")
      (node (ref "IC4") (pin "4") (pinfunction "RA5/~{MCLR}/VPP_4") (pintype "bidirectional"))
    )
    (net (code "92") (name "unconnected-(IC4-RA6-Pad15)") (class "Default")
      (node (ref "IC4") (pin "15") (pinfunction "RA6_15") (pintype "bidirectional"))
    )
    (net (code "93") (name "unconnected-(IC4-RA7-Pad16)") (class "Default")
      (node (ref "IC4") (pin "16") (pinfunction "RA7_16") (pintype "bidirectional"))
    )
    (net (code "94") (name "unconnected-(IC5-RA0-Pad17)") (class "Default")
      (node (ref "IC5") (pin "17") (pinfunction "RA0_17") (pintype "bidirectional"))
    )
    (net (code "95") (name "unconnected-(IC5-RA1-Pad18)") (class "Default")
      (node (ref "IC5") (pin "18") (pinfunction "RA1_18") (pintype "bidirectional"))
    )
    (net (code "96") (name "unconnected-(IC5-RA2-Pad1)") (class "Default")
      (node (ref "IC5") (pin "1") (pinfunction "RA2_1") (pintype "bidirectional"))
    )
    (net (code "97") (name "unconnected-(IC5-RA3-Pad2)") (class "Default")
      (node (ref "IC5") (pin "2") (pinfunction "RA3_2") (pintype "bidirectional"))
    )
    (net (code "98") (name "unconnected-(IC5-RA4-Pad3)") (class "Default")
      (node (ref "IC5") (pin "3") (pinfunction "RA4_3") (pintype "bidirectional"))
    )
    (net (code "99") (name "unconnected-(IC5-RA5{slash}~{MCLR}{slash}VPP-Pad4)") (class "Default")
      (node (ref "IC5") (pin "4") (pinfunction "RA5/~{MCLR}/VPP_4") (pintype "bidirectional"))
    )
    (net (code "100") (name "unconnected-(IC5-RA6-Pad15)") (class "Default")
      (node (ref "IC5") (pin "15") (pinfunction "RA6_15") (pintype "bidirectional"))
    )
    (net (code "101") (name "unconnected-(IC5-RA7-Pad16)") (class "Default")
      (node (ref "IC5") (pin "16") (pinfunction "RA7_16") (pintype "bidirectional"))
    )
    (net (code "102") (name "unconnected-(IC6-RA0-Pad17)") (class "Default")
      (node (ref "IC6") (pin "17") (pinfunction "RA0_17") (pintype "bidirectional"))
    )
    (net (code "103") (name "unconnected-(IC6-RA1-Pad18)") (class "Default")
      (node (ref "IC6") (pin "18") (pinfunction "RA1_18") (pintype "bidirectional"))
    )
    (net (code "104") (name "unconnected-(IC6-RA2-Pad1)") (class "Default")
      (node (ref "IC6") (pin "1") (pinfunction "RA2_1") (pintype "bidirectional"))
    )
    (net (code "105") (name "unconnected-(IC6-RA3-Pad2)") (class "Default")
      (node (ref "IC6") (pin "2") (pinfunction "RA3_2") (pintype "bidirectional"))
    )
    (net (code "106") (name "unconnected-(IC6-RA4-Pad3)") (class "Default")
      (node (ref "IC6") (pin "3") (pinfunction "RA4_3") (pintype "bidirectional"))
    )
    (net (code "107") (name "unconnected-(IC6-RA5{slash}~{MCLR}{slash}VPP-Pad4)") (class "Default")
      (node (ref "IC6") (pin "4") (pinfunction "RA5/~{MCLR}/VPP_4") (pintype "bidirectional"))
    )
    (net (code "108") (name "unconnected-(IC6-RA6-Pad15)") (class "Default")
      (node (ref "IC6") (pin "15") (pinfunction "RA6_15") (pintype "bidirectional"))
    )
    (net (code "109") (name "unconnected-(IC6-RA7-Pad16)") (class "Default")
      (node (ref "IC6") (pin "16") (pinfunction "RA7_16") (pintype "bidirectional"))
    )
    (net (code "110") (name "unconnected-(IC7-RA0-Pad17)") (class "Default")
      (node (ref "IC7") (pin "17") (pinfunction "RA0_17") (pintype "bidirectional"))
    )
    (net (code "111") (name "unconnected-(IC7-RA1-Pad18)") (class "Default")
      (node (ref "IC7") (pin "18") (pinfunction "RA1_18") (pintype "bidirectional"))
    )
    (net (code "112") (name "unconnected-(IC7-RA2-Pad1)") (class "Default")
      (node (ref "IC7") (pin "1") (pinfunction "RA2_1") (pintype "bidirectional"))
    )
    (net (code "113") (name "unconnected-(IC7-RA3-Pad2)") (class "Default")
      (node (ref "IC7") (pin "2") (pinfunction "RA3_2") (pintype "bidirectional"))
    )
    (net (code "114") (name "unconnected-(IC7-RA4-Pad3)") (class "Default")
      (node (ref "IC7") (pin "3") (pinfunction "RA4_3") (pintype "bidirectional"))
    )
    (net (code "115") (name "unconnected-(IC7-RA5{slash}~{MCLR}{slash}VPP-Pad4)") (class "Default")
      (node (ref "IC7") (pin "4") (pinfunction "RA5/~{MCLR}/VPP_4") (pintype "bidirectional"))
    )
    (net (code "116") (name "unconnected-(IC7-RA6-Pad15)") (class "Default")
      (node (ref "IC7") (pin "15") (pinfunction "RA6_15") (pintype "bidirectional"))
    )
    (net (code "117") (name "unconnected-(IC7-RA7-Pad16)") (class "Default")
      (node (ref "IC7") (pin "16") (pinfunction "RA7_16") (pintype "bidirectional"))
    )
    (net (code "118") (name "シリアルデータ") (class "Default")
      (node (ref "IC1") (pin "22") (pinfunction "RB1_22") (pintype "bidirectional"))
      (node (ref "SV1") (pin "2") (pinfunction "2_2") (pintype "passive"))
    )
    (net (code "119") (name "電池+") (class "Default")
      (node (ref "JP11") (pin "3") (pinfunction "3_3") (pintype "passive"))
    )
    (net (code "120") (name "電池-") (class "Default")
      (node (ref "JP12") (pin "3") (pinfunction "3_3") (pintype "passive"))
    )
  )
)
